# lcd.net
KiCad netlist of a schematic drawn in EAGLE
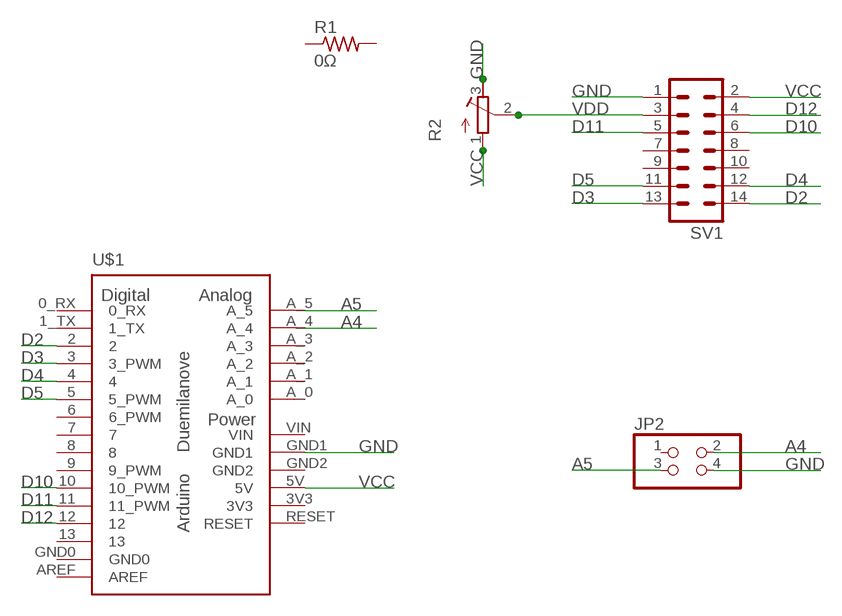
[diagram p0: schematic, sheet 1]

(export (version "E")
  (design (tool "Eeschema 10.0.6"))
  (components
    (comp (ref "JP2")
      (value "PINHD-2X2")
      (footprint "eagle-import:2X02")
      (libsource (lib "eagle-import") (part "PINHD-2X2"))
    )
    (comp (ref "R1")
      (value "0Ω")
      (footprint "eagle-import:M1206")
      (libsource (lib "eagle-import") (part "R-US_M1206"))
    )
    (comp (ref "R2")
      (value "R-TRIMM5W")
      (footprint "eagle-import:RTRIM5W")
      (libsource (lib "eagle-import") (part "R-TRIMM5W"))
    )
    (comp (ref "SV1")
      (value "MA07-2")
      (footprint "eagle-import:MA07-2")
      (libsource (lib "eagle-import") (part "MA07-2"))
    )
    (comp (ref "U$1")
      (value "ARDUINO-USBLONG_PADS_TEXT")
      (footprint "eagle-import:SHIELD")
      (libsource (lib "eagle-import") (part "ARDUINO-USBLONG_PADS_TEXT"))
    )
  )
  (nets
    (net (code "1") (name "/3V3") (class "Default")
      (node (ref "U$1") (pin "3V3") (pinfunction "3V3_3V3") (pintype "power_in"))
    )
    (net (code "2") (name "/A4") (class "Default")
      (node (ref "JP2") (pin "2") (pinfunction "2_2") (pintype "passive"))
      (node (ref "U$1") (pin "A_4") (pinfunction "A_4_A_4") (pintype "input"))
    )
    (net (code "3") (name "/A5") (class "Default")
      (node (ref "JP2") (pin "3") (pinfunction "3_3") (pintype "passive"))
      (node (ref "U$1") (pin "A_5") (pinfunction "A_5_A_5") (pintype "input"))
    )
    (net (code "4") (name "/D2") (class "Default")
      (node (ref "SV1") (pin "14") (pinfunction "14_14") (pintype "passive"))
      (node (ref "U$1") (pin "2") (pinfunction "2_2") (pintype "bidirectional"))
    )
    (net (code "5") (name "/D3") (class "Default")
      (node (ref "SV1") (pin "13") (pinfunction "13_13") (pintype "passive"))
      (node (ref "U$1") (pin "3") (pinfunction "3_PWM_3") (pintype "bidirectional"))
    )
    (net (code "6") (name "/D4") (class "Default")
      (node (ref "SV1") (pin "12") (pinfunction "12_12") (pintype "passive"))
      (node (ref "U$1") (pin "4") (pinfunction "4_4") (pintype "bidirectional"))
    )
    (net (code "7") (name "/D5") (class "Default")
      (node (ref "SV1") (pin "11") (pinfunction "11_11") (pintype "passive"))
      (node (ref "U$1") (pin "5") (pinfunction "5_PWM_5") (pintype "bidirectional"))
    )
    (net (code "8") (name "/D10") (class "Default")
      (node (ref "SV1") (pin "6") (pinfunction "6_6") (pintype "passive"))
      (node (ref "U$1") (pin "10") (pinfunction "10_PWM_10") (pintype "bidirectional"))
    )
    (net (code "9") (name "/D11") (class "Default")
      (node (ref "SV1") (pin "5") (pinfunction "5_5") (pintype "passive"))
      (node (ref "U$1") (pin "11") (pinfunction "11_PWM_11") (pintype "bidirectional"))
    )
    (net (code "10") (name "/D12") (class "Default")
      (node (ref "SV1") (pin "4") (pinfunction "4_4") (pintype "passive"))
      (node (ref "U$1") (pin "12") (pinfunction "12_12") (pintype "bidirectional"))
    )
    (net (code "11") (name "/GND") (class "Default")
      (node (ref "JP2") (pin "4") (pinfunction "4_4") (pintype "passive"))
      (node (ref "R2") (pin "3") (pinfunction "E_3") (pintype "passive"))
      (node (ref "SV1") (pin "1") (pinfunction "1_1") (pintype "passive"))
      (node (ref "U$1") (pin "GND1") (pinfunction "GND1_GND1") (pintype "power_in"))
    )
    (net (code "12") (name "/GND0") (class "Default")
      (node (ref "U$1") (pin "GND0") (pinfunction "GND0_GND0") (pintype "power_in"))
    )
    (net (code "13") (name "/GND2") (class "Default")
      (node (ref "U$1") (pin "GND2") (pinfunction "GND2_GND2") (pintype "power_in"))
    )
    (net (code "14") (name "/VCC") (class "Default")
      (node (ref "R2") (pin "1") (pinfunction "A_1") (pintype "passive"))
      (node (ref "SV1") (pin "2") (pinfunction "2_2") (pintype "passive"))
      (node (ref "U$1") (pin "5V") (pinfunction "5V_5V") (pintype "power_in"))
    )
    (net (code "15") (name "/VDD") (class "Default")
      (node (ref "R2") (pin "2") (pinfunction "S_2") (pintype "passive"))
      (node (ref "SV1") (pin "3") (pinfunction "3_3") (pintype "passive"))
    )
    (net (code "16") (name "/VIN") (class "Default")
      (node (ref "U$1") (pin "VIN") (pinfunction "VIN_VIN") (pintype "power_in"))
    )
    (net (code "17") (name "unconnected-(JP2-Pad1)") (class "Default")
      (node (ref "JP2") (pin "1") (pinfunction "1_1") (pintype "passive"))
    )
    (net (code "18") (name "unconnected-(R1-Pad1)") (class "Default")
      (node (ref "R1") (pin "1") (pinfunction "1_1") (pintype "passive"))
    )
    (net (code "19") (name "unconnected-(R1-Pad2)") (class "Default")
      (node (ref "R1") (pin "2") (pinfunction "2_2") (pintype "passive"))
    )
    (net (code "20") (name "unconnected-(SV1-Pad7)") (class "Default")
      (node (ref "SV1") (pin "7") (pinfunction "7_7") (pintype "passive"))
    )
    (net (code "21") (name "unconnected-(SV1-Pad8)") (class "Default")
      (node (ref "SV1") (pin "8") (pinfunction "8_8") (pintype "passive"))
    )
    (net (code "22") (name "unconnected-(SV1-Pad9)") (class "Default")
      (node (ref "SV1") (pin "9") (pinfunction "9_9") (pintype "passive"))
    )
    (net (code "23") (name "unconnected-(SV1-Pad10)") (class "Default")
      (node (ref "SV1") (pin "10") (pinfunction "10_10") (pintype "passive"))
    )
    (net (code "24") (name "unconnected-(U$1-6_PWM-Pad6)") (class "Default")
      (node (ref "U$1") (pin "6") (pinfunction "6_PWM_6") (pintype "bidirectional"))
    )
    (net (code "25") (name "unconnected-(U$1-9_PWM-Pad9)") (class "Default")
      (node (ref "U$1") (pin "9") (pinfunction "9_PWM_9") (pintype "bidirectional"))
    )
    (net (code "26") (name "unconnected-(U$1-Pad0_RX)") (class "Default")
      (node (ref "U$1") (pin "0_RX") (pinfunction "0_RX_0_RX") (pintype "bidirectional"))
    )
    (net (code "27") (name "unconnected-(U$1-Pad1_TX)") (class "Default")
      (node (ref "U$1") (pin "1_TX") (pinfunction "1_TX_1_TX") (pintype "bidirectional"))
    )
    (net (code "28") (name "unconnected-(U$1-Pad7)") (class "Default")
      (node (ref "U$1") (pin "7") (pinfunction "7_7") (pintype "bidirectional"))
    )
    (net (code "29") (name "unconnected-(U$1-Pad8)") (class "Default")
      (node (ref "U$1") (pin "8") (pinfunction "8_8") (pintype "bidirectional"))
    )
    (net (code "30") (name "unconnected-(U$1-Pad13)") (class "Default")
      (node (ref "U$1") (pin "13") (pinfunction "13_13") (pintype "bidirectional"))
    )
    (net (code "31") (name "unconnected-(U$1-PadAREF)") (class "Default")
      (node (ref "U$1") (pin "AREF") (pinfunction "AREF_AREF") (pintype "bidirectional"))
    )
    (net (code "32") (name "unconnected-(U$1-PadA_0)") (class "Default")
      (node (ref "U$1") (pin "A_0") (pinfunction "A_0_A_0") (pintype "input"))
    )
    (net (code "33") (name "unconnected-(U$1-PadA_1)") (class "Default")
      (node (ref "U$1") (pin "A_1") (pinfunction "A_1_A_1") (pintype "input"))
    )
    (net (code "34") (name "unconnected-(U$1-PadA_2)") (class "Default")
      (node (ref "U$1") (pin "A_2") (pinfunction "A_2_A_2") (pintype "input"))
    )
    (net (code "35") (name "unconnected-(U$1-PadA_3)") (class "Default")
      (node (ref "U$1") (pin "A_3") (pinfunction "A_3_A_3") (pintype "input"))
    )
    (net (code "36") (name "unconnected-(U$1-PadRESET)") (class "Default")
      (node (ref "U$1") (pin "RESET") (pinfunction "RESET_RESET") (pintype "input"))
    )
  )
)
